# pic_dfn.net
KiCad netlist of a schematic drawn in EAGLE
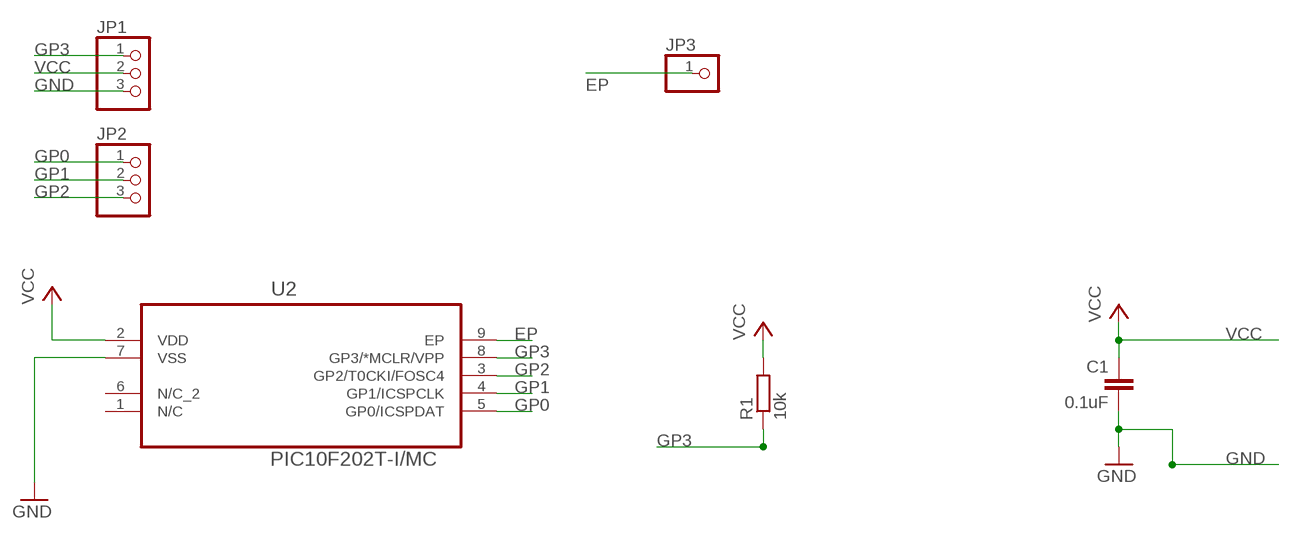
[diagram p0: schematic, sheet 1]

(export (version "E")
  (design (tool "Eeschema 10.0.6"))
  (components
    (comp (ref "C1")
      (value "0.1uF")
      (footprint "eagle-import:C0603")
      (libsource (lib "eagle-import") (part "C-EUC0603"))
    )
    (comp (ref "JP1")
      (value "PINHD-1X3")
      (footprint "eagle-import:1X03")
      (libsource (lib "eagle-import") (part "PINHD-1X3"))
    )
    (comp (ref "JP2")
      (value "PINHD-1X3")
      (footprint "eagle-import:1X03")
      (libsource (lib "eagle-import") (part "PINHD-1X3"))
    )
    (comp (ref "JP3")
      (value "PINHD-1X1")
      (footprint "eagle-import:1X01")
      (libsource (lib "eagle-import") (part "PINHD-1X1"))
    )
    (comp (ref "R1")
      (value "10k")
      (footprint "eagle-import:R0603")
      (libsource (lib "eagle-import") (part "R-EU_R0603"))
    )
    (comp (ref "U2")
      (value "PIC10F202T-I/MC")
      (footprint "eagle-import:DFN200X300X100-9N")
      (libsource (lib "eagle-import") (part "PIC10F202T-I/MC"))
    )
  )
  (nets
    (net (code "1") (name "/EP") (class "Default")
      (node (ref "JP3") (pin "1") (pinfunction "1_1") (pintype "passive"))
      (node (ref "U2") (pin "9") (pinfunction "EP_9") (pintype "passive"))
    )
    (net (code "2") (name "/GP0") (class "Default")
      (node (ref "JP2") (pin "1") (pinfunction "1_1") (pintype "passive"))
      (node (ref "U2") (pin "5") (pinfunction "GP0/ICSPDAT_5") (pintype "output"))
    )
    (net (code "3") (name "/GP1") (class "Default")
      (node (ref "JP2") (pin "2") (pinfunction "2_2") (pintype "passive"))
      (node (ref "U2") (pin "4") (pinfunction "GP1/ICSPCLK_4") (pintype "output"))
    )
    (net (code "4") (name "/GP2") (class "Default")
      (node (ref "JP2") (pin "3") (pinfunction "3_3") (pintype "passive"))
      (node (ref "U2") (pin "3") (pinfunction "GP2/T0CKI/FOSC4_3") (pintype "output"))
    )
    (net (code "5") (name "/GP3") (class "Default")
      (node (ref "JP1") (pin "1") (pinfunction "1_1") (pintype "passive"))
      (node (ref "R1") (pin "1") (pinfunction "1_1") (pintype "passive"))
      (node (ref "U2") (pin "8") (pinfunction "GP3/*MCLR/VPP_8") (pintype "output"))
    )
    (net (code "6") (name "GND") (class "Default")
      (node (ref "C1") (pin "2") (pinfunction "2_2") (pintype "passive"))
      (node (ref "JP1") (pin "3") (pinfunction "3_3") (pintype "passive"))
      (node (ref "U2") (pin "7") (pinfunction "VSS_7") (pintype "passive"))
    )
    (net (code "7") (name "VCC") (class "Default")
      (node (ref "C1") (pin "1") (pinfunction "1_1") (pintype "passive"))
      (node (ref "JP1") (pin "2") (pinfunction "2_2") (pintype "passive"))
      (node (ref "R1") (pin "2") (pinfunction "2_2") (pintype "passive"))
      (node (ref "U2") (pin "2") (pinfunction "VDD_2") (pintype "power_in"))
    )
    (net (code "8") (name "unconnected-(U2-N{slash}C-Pad1)") (class "Default")
      (node (ref "U2") (pin "1") (pinfunction "N/C_1") (pintype "no_connect"))
    )
    (net (code "9") (name "unconnected-(U2-N{slash}C_2-Pad6)") (class "Default")
      (node (ref "U2") (pin "6") (pinfunction "N/C_2_6") (pintype "no_connect"))
    )
  )
)
